# Digital_Camera.net
KiCad netlist of a schematic drawn in Altium Designer
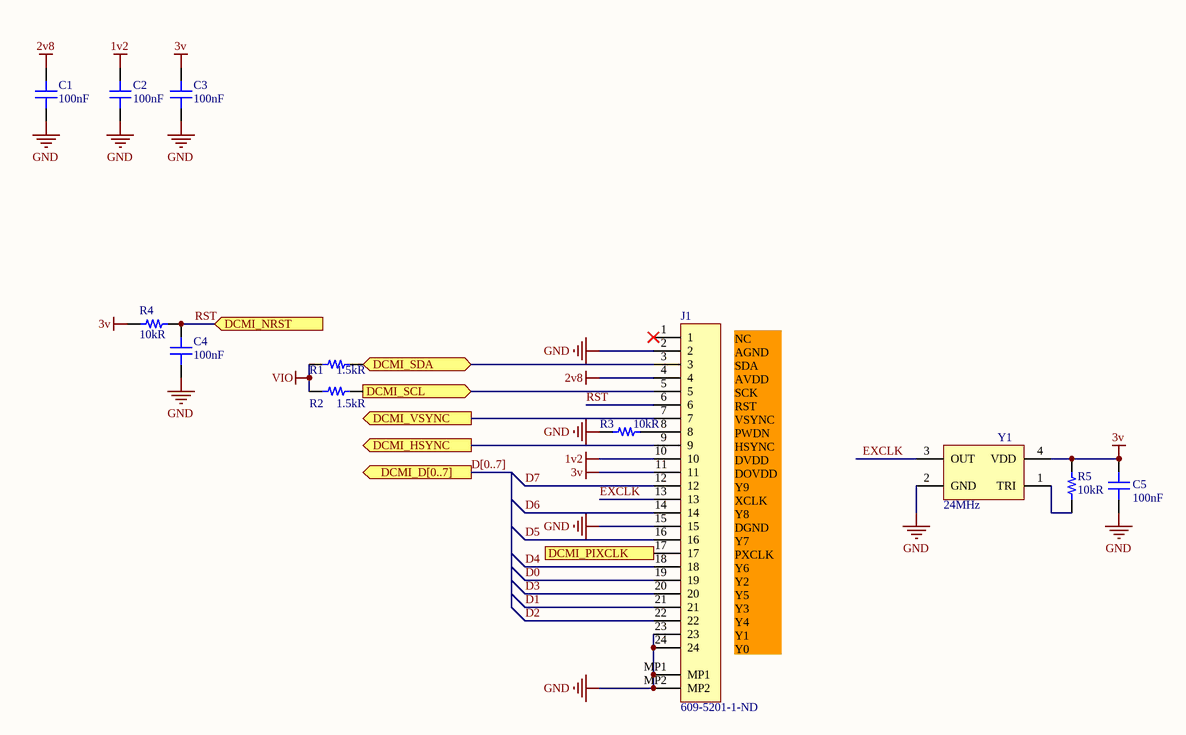
[diagram p0: Digital Camera.SchDoc]

(export (version "E")
  (design (tool "Eeschema 10.0.6"))
  (components
    (comp (ref "C1")
      (value "100nF")
      (footprint "CAP 0603/1608")
      (description "Ceramic, SMT Capacitor")
      (fields
        (field (name "MANUFACTURER") "Samsung")
        (field (name "MANUFACTURER PART NUMBER") "CL10B104JB8NNNC")
      )
      (libsource (lib "yildizIoT Library") (part "Capacitor - Ceramic"))
    )
    (comp (ref "C2")
      (value "100nF")
      (footprint "CAP 0603/1608")
      (description "Ceramic, SMT Capacitor")
      (fields
        (field (name "MANUFACTURER") "Samsung")
        (field (name "MANUFACTURER PART NUMBER") "CL10B104JB8NNNC")
      )
      (libsource (lib "yildizIoT Library") (part "Capacitor - Ceramic"))
    )
    (comp (ref "C3")
      (value "100nF")
      (footprint "CAP 0603/1608")
      (description "Ceramic, SMT Capacitor")
      (fields
        (field (name "MANUFACTURER") "Samsung")
        (field (name "MANUFACTURER PART NUMBER") "CL10B104JB8NNNC")
      )
      (libsource (lib "yildizIoT Library") (part "Capacitor - Ceramic"))
    )
    (comp (ref "C4")
      (value "100nF")
      (footprint "CAP 0603/1608")
      (description "Ceramic, SMT Capacitor")
      (fields
        (field (name "MANUFACTURER") "Samsung")
        (field (name "MANUFACTURER PART NUMBER") "CL10B104JB8NNNC")
      )
      (libsource (lib "yildizIoT Library") (part "Capacitor - Ceramic"))
    )
    (comp (ref "C5")
      (value "100nF")
      (footprint "CAP 0603/1608")
      (description "Ceramic, SMT Capacitor")
      (fields
        (field (name "MANUFACTURER") "Samsung")
        (field (name "MANUFACTURER PART NUMBER") "CL10B104JB8NNNC")
      )
      (libsource (lib "yildizIoT Library") (part "Capacitor - Ceramic"))
    )
    (comp (ref "J1")
      (value "SFV24R-3STBE1HLF")
      (footprint "Amphenol SFV24R-1STE1HLF")
      (description "Connector")
      (fields
        (field (name "SUPPLIER PART NUMBER 1") "609-5201-1-ND")
        (field (name "MANUFACTURER") "Amphenol FCI")
      )
      (libsource (lib "yildizIoT Library") (part "FPC-24"))
    )
    (comp (ref "R1")
      (value "1.5kR")
      (footprint "RES 0603/1608")
      (description "Ceramic, SMT Capacitor")
      (fields
        (field (name "MANUFACTURER") "Yageo")
        (field (name "MANUFACTURER PART NUMBER") "RC0603FR-071K5L")
      )
      (libsource (lib "yildizIoT Library") (part "Resistor_Chip"))
    )
    (comp (ref "R2")
      (value "1.5kR")
      (footprint "RES 0603/1608")
      (description "Ceramic, SMT Capacitor")
      (fields
        (field (name "MANUFACTURER") "Yageo")
        (field (name "MANUFACTURER PART NUMBER") "RC0603FR-071K5L")
      )
      (libsource (lib "yildizIoT Library") (part "Resistor_Chip"))
    )
    (comp (ref "R3")
      (value "10kR")
      (footprint "RES 0603/1608")
      (description "Ceramic, SMT Capacitor")
      (fields
        (field (name "MANUFACTURER") "Stackpole Electronics")
        (field (name "MANUFACTURER PART NUMBER") "RNCP0603FTD10K0")
      )
      (libsource (lib "yildizIoT Library") (part "Resistor_Chip"))
    )
    (comp (ref "R4")
      (value "10kR")
      (footprint "RES 0603/1608")
      (description "Ceramic, SMT Capacitor")
      (fields
        (field (name "MANUFACTURER") "Stackpole Electronics")
        (field (name "MANUFACTURER PART NUMBER") "RNCP0603FTD10K0")
      )
      (libsource (lib "yildizIoT Library") (part "Resistor_Chip"))
    )
    (comp (ref "R5")
      (value "10kR")
      (footprint "RES 0603/1608")
      (description "Ceramic, SMT Capacitor")
      (fields
        (field (name "MANUFACTURER") "Stackpole Electronics")
        (field (name "MANUFACTURER PART NUMBER") "RNCP0603FTD10K0")
      )
      (libsource (lib "yildizIoT Library") (part "Resistor_Chip"))
    )
    (comp (ref "Y1")
      (value "24MHz")
      (footprint "Abracon ASTX-11")
      (description "OSC XO 1.544MHZ CMOS SMD")
      (fields
        (field (name "MANUFACTURER") "ECS Inc.")
        (field (name "MANUFACTURER PART NUMBER") "ECS-3225MV-240-CN-TR")
      )
      (libsource (lib "Celestial Library Database") (part "Abracon XO ASD"))
    )
  )
  (nets
    (net (code "1") (name "/D0") (class "Default")
      (node (ref "J1") (pin "19") (pinfunction "19_19") (pintype "passive"))
    )
    (net (code "2") (name "/D1") (class "Default")
      (node (ref "J1") (pin "21") (pinfunction "21_21") (pintype "passive"))
    )
    (net (code "3") (name "/D2") (class "Default")
      (node (ref "J1") (pin "22") (pinfunction "22_22") (pintype "passive"))
    )
    (net (code "4") (name "/D3") (class "Default")
      (node (ref "J1") (pin "20") (pinfunction "20_20") (pintype "passive"))
    )
    (net (code "5") (name "/D4") (class "Default")
      (node (ref "J1") (pin "18") (pinfunction "18_18") (pintype "passive"))
    )
    (net (code "6") (name "/D5") (class "Default")
      (node (ref "J1") (pin "16") (pinfunction "16_16") (pintype "passive"))
    )
    (net (code "7") (name "/D6") (class "Default")
      (node (ref "J1") (pin "14") (pinfunction "14_14") (pintype "passive"))
    )
    (net (code "8") (name "/D7") (class "Default")
      (node (ref "J1") (pin "12") (pinfunction "12_12") (pintype "passive"))
    )
    (net (code "9") (name "/DCMI_HSYNC") (class "Default")
      (node (ref "J1") (pin "9") (pinfunction "9_9") (pintype "passive"))
    )
    (net (code "10") (name "/DCMI_PIXCLK") (class "Default")
      (node (ref "J1") (pin "17") (pinfunction "17_17") (pintype "passive"))
    )
    (net (code "11") (name "/DCMI_SCL") (class "Default")
      (node (ref "J1") (pin "5") (pinfunction "5_5") (pintype "passive"))
      (node (ref "R2") (pin "1") (pinfunction "1_1") (pintype "passive"))
    )
    (net (code "12") (name "/DCMI_SDA") (class "Default")
      (node (ref "J1") (pin "3") (pinfunction "3_3") (pintype "passive"))
      (node (ref "R1") (pin "1") (pinfunction "1_1") (pintype "passive"))
    )
    (net (code "13") (name "/DCMI_VSYNC") (class "Default")
      (node (ref "J1") (pin "7") (pinfunction "7_7") (pintype "passive"))
    )
    (net (code "15") (name "/EXCLK") (class "Default")
      (node (ref "J1") (pin "13") (pinfunction "13_13") (pintype "passive"))
      (node (ref "Y1") (pin "3") (pinfunction "OUT_3") (pintype "passive"))
    )
    (net (code "16") (name "/RST") (class "Default")
      (node (ref "C4") (pin "2") (pinfunction "2_2") (pintype "passive"))
      (node (ref "J1") (pin "6") (pinfunction "6_6") (pintype "passive"))
      (node (ref "R4") (pin "1") (pinfunction "1_1") (pintype "passive"))
    )
    (net (code "17") (name "1v2") (class "Default")
      (node (ref "C2") (pin "2") (pinfunction "2_2") (pintype "passive"))
      (node (ref "J1") (pin "10") (pinfunction "10_10") (pintype "passive"))
    )
    (net (code "18") (name "2v8") (class "Default")
      (node (ref "C1") (pin "2") (pinfunction "2_2") (pintype "passive"))
      (node (ref "J1") (pin "4") (pinfunction "4_4") (pintype "passive"))
    )
    (net (code "19") (name "3v") (class "Default")
      (node (ref "C3") (pin "2") (pinfunction "2_2") (pintype "passive"))
      (node (ref "C5") (pin "2") (pinfunction "2_2") (pintype "passive"))
      (node (ref "J1") (pin "11") (pinfunction "11_11") (pintype "passive"))
      (node (ref "R4") (pin "2") (pinfunction "2_2") (pintype "passive"))
      (node (ref "R5") (pin "1") (pinfunction "1_1") (pintype "passive"))
      (node (ref "Y1") (pin "4") (pinfunction "VDD_4") (pintype "passive"))
    )
    (net (code "20") (name "GND") (class "Default")
      (node (ref "C1") (pin "1") (pinfunction "1_1") (pintype "passive"))
      (node (ref "C2") (pin "1") (pinfunction "1_1") (pintype "passive"))
      (node (ref "C3") (pin "1") (pinfunction "1_1") (pintype "passive"))
      (node (ref "C4") (pin "1") (pinfunction "1_1") (pintype "passive"))
      (node (ref "C5") (pin "1") (pinfunction "1_1") (pintype "passive"))
      (node (ref "J1") (pin "15") (pinfunction "15_15") (pintype "passive"))
      (node (ref "J1") (pin "2") (pinfunction "2_2") (pintype "passive"))
      (node (ref "J1") (pin "23") (pinfunction "23_23") (pintype "passive"))
      (node (ref "J1") (pin "24") (pinfunction "24_24") (pintype "passive"))
      (node (ref "J1") (pin "MP1") (pinfunction "MP1_MP1") (pintype "passive"))
      (node (ref "J1") (pin "MP2") (pinfunction "MP2_MP2") (pintype "passive"))
      (node (ref "R3") (pin "1") (pinfunction "1_1") (pintype "passive"))
      (node (ref "Y1") (pin "2") (pinfunction "GND_2") (pintype "passive"))
    )
    (net (code "21") (name "Net-(J1-Pad8)") (class "Default")
      (node (ref "J1") (pin "8") (pinfunction "8_8") (pintype "passive"))
      (node (ref "R3") (pin "2") (pinfunction "2_2") (pintype "passive"))
    )
    (net (code "22") (name "Net-(Y1-TRI)") (class "Default")
      (node (ref "R5") (pin "2") (pinfunction "2_2") (pintype "passive"))
      (node (ref "Y1") (pin "1") (pinfunction "TRI_1") (pintype "passive"))
    )
    (net (code "23") (name "VIO") (class "Default")
      (node (ref "R1") (pin "2") (pinfunction "2_2") (pintype "passive"))
      (node (ref "R2") (pin "2") (pinfunction "2_2") (pintype "passive"))
    )
    (net (code "24") (name "unconnected-(J1-Pad1)") (class "Default")
      (node (ref "J1") (pin "1") (pinfunction "1_1") (pintype "passive+no_connect"))
    )
  )
)
